# ADC_8CH.net
KiCad netlist of a schematic drawn in Altium Designer
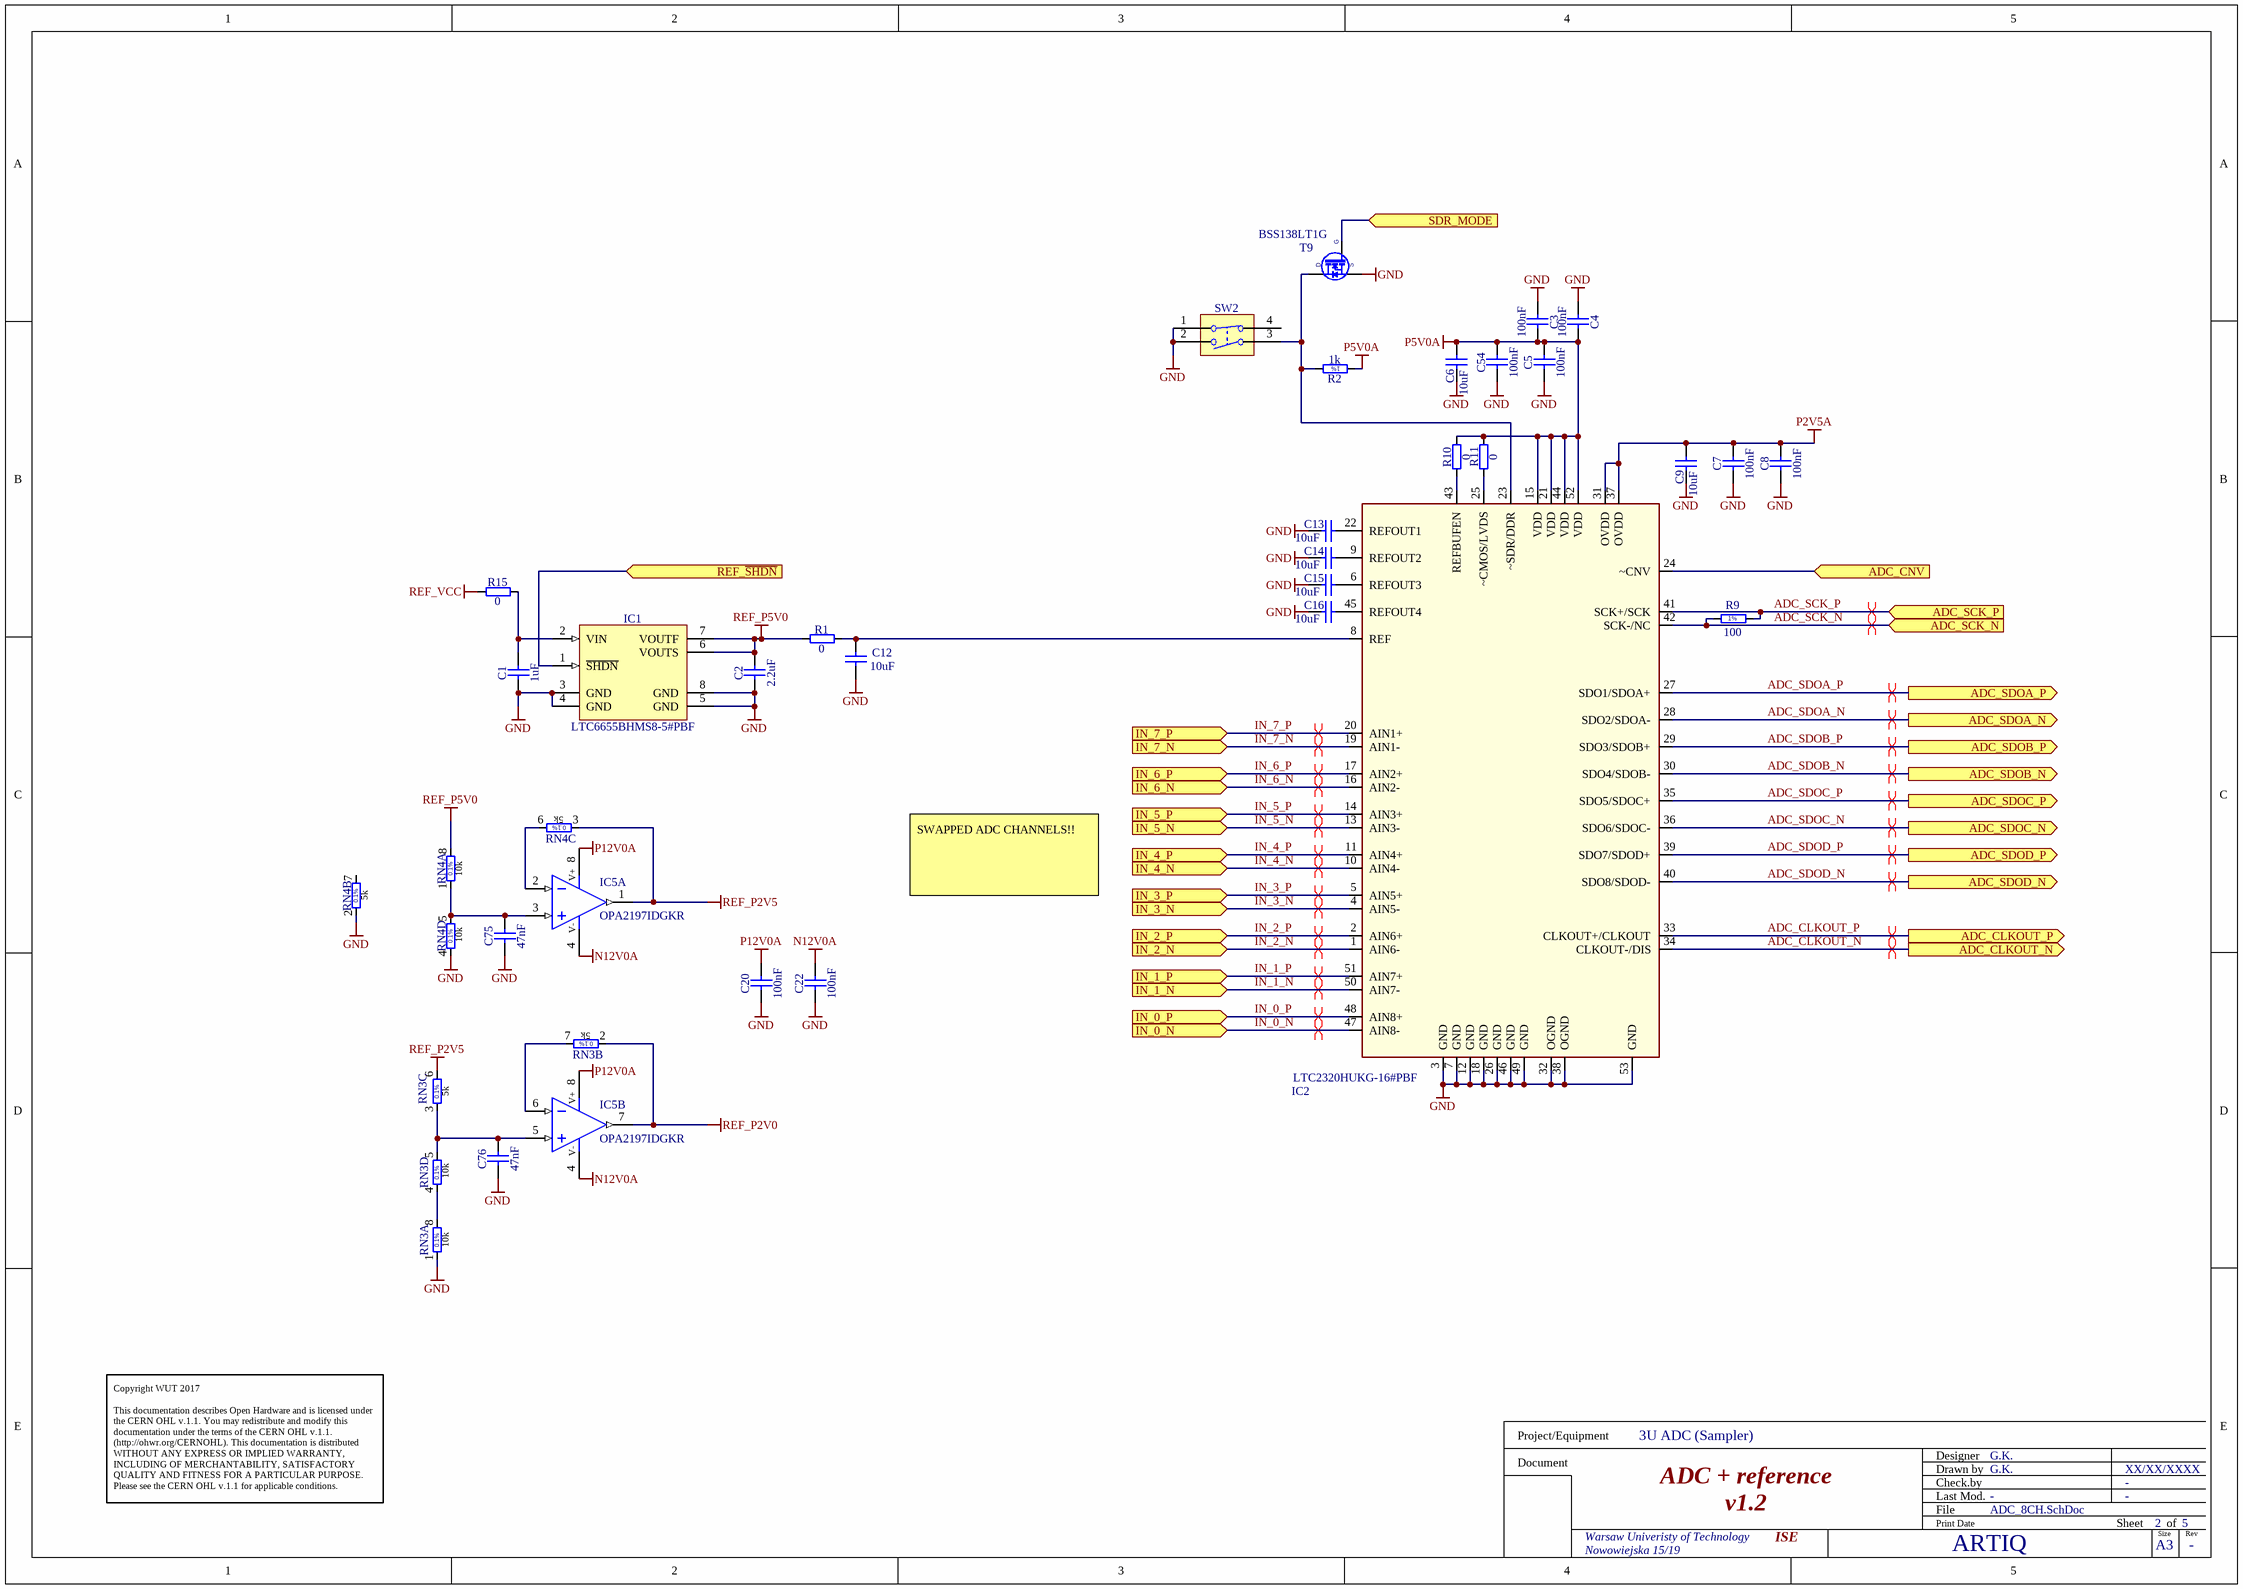
[diagram p0: ADC_8CH.SchDoc]

(export (version "E")
  (design (tool "Eeschema 10.0.6"))
  (components
    (comp (ref "C1")
      (value "1uF")
      (footprint "CAPC1608X87N")
      (description "Non-polarised capacitor")
      (fields
        (field (name "PART NUMBER") "CC0603_1UF_25V_10%_X7R")
        (field (name "VOLTAGE") "25V")
        (field (name "AUTHOR") "CERN DEM JLC")
      )
      (libsource (lib "Capacitors") (part "Capacitor - non polarized"))
    )
    (comp (ref "C2")
      (value "2.2uF")
      (footprint "CAPC1608X87N")
      (description "Non-polarised capacitor")
      (fields
        (field (name "PART NUMBER") "CC0603_2.2UF_16V_10%_X5R")
        (field (name "VOLTAGE") "16V")
        (field (name "AUTHOR") "CERN DEM JLC")
      )
      (libsource (lib "Capacitors") (part "Capacitor - non polarized"))
    )
    (comp (ref "C3")
      (value "100nF")
      (footprint "CAPC1608X87N")
      (description "Non-polarised capacitor")
      (fields
        (field (name "PART NUMBER") "CC0603_100NF_50V_10%_X7R")
        (field (name "VOLTAGE") "50V")
        (field (name "AUTHOR") "CERN DEM JLC")
      )
      (libsource (lib "Capacitors") (part "Capacitor - non polarized"))
    )
    (comp (ref "C4")
      (value "100nF")
      (footprint "CAPC1608X87N")
      (description "Non-polarised capacitor")
      (fields
        (field (name "PART NUMBER") "CC0603_100NF_50V_10%_X7R")
        (field (name "VOLTAGE") "50V")
        (field (name "AUTHOR") "CERN DEM JLC")
      )
      (libsource (lib "Capacitors") (part "Capacitor - non polarized"))
    )
    (comp (ref "C5")
      (value "100nF")
      (footprint "CAPC1608X87N")
      (description "Non-polarised capacitor")
      (fields
        (field (name "PART NUMBER") "CC0603_100NF_50V_10%_X7R")
        (field (name "VOLTAGE") "50V")
        (field (name "AUTHOR") "CERN DEM JLC")
      )
      (libsource (lib "Capacitors") (part "Capacitor - non polarized"))
    )
    (comp (ref "C6")
      (value "10uF")
      (footprint "CAPC2012X95N")
      (description "Non-polarised capacitor")
      (fields
        (field (name "PART NUMBER") "CC0805_10UF_25V_10%_X5R")
        (field (name "VOLTAGE") "25V")
        (field (name "AUTHOR") "CERN DEM JLC")
      )
      (libsource (lib "Capacitors") (part "Capacitor - non polarized"))
    )
    (comp (ref "C7")
      (value "100nF")
      (footprint "CAPC1608X87N")
      (description "Non-polarised capacitor")
      (fields
        (field (name "PART NUMBER") "CC0603_100NF_50V_10%_X7R")
        (field (name "VOLTAGE") "50V")
        (field (name "AUTHOR") "CERN DEM JLC")
      )
      (libsource (lib "Capacitors") (part "Capacitor - non polarized"))
    )
    (comp (ref "C8")
      (value "100nF")
      (footprint "CAPC1608X87N")
      (description "Non-polarised capacitor")
      (fields
        (field (name "PART NUMBER") "CC0603_100NF_50V_10%_X7R")
        (field (name "VOLTAGE") "50V")
        (field (name "AUTHOR") "CERN DEM JLC")
      )
      (libsource (lib "Capacitors") (part "Capacitor - non polarized"))
    )
    (comp (ref "C9")
      (value "10uF")
      (footprint "CAPC2012X95N")
      (description "Non-polarised capacitor")
      (fields
        (field (name "PART NUMBER") "CC0805_10UF_25V_10%_X5R")
        (field (name "VOLTAGE") "25V")
        (field (name "AUTHOR") "CERN DEM JLC")
      )
      (libsource (lib "Capacitors") (part "Capacitor - non polarized"))
    )
    (comp (ref "C12")
      (value "10uF")
      (footprint "CAPC2012X95N")
      (description "Non-polarised capacitor")
      (fields
        (field (name "PART NUMBER") "CC0805_10UF_25V_10%_X5R")
        (field (name "VOLTAGE") "25V")
        (field (name "AUTHOR") "CERN DEM JLC")
      )
      (libsource (lib "Capacitors") (part "Capacitor - non polarized"))
    )
    (comp (ref "C13")
      (value "10uF")
      (footprint "CAPC2012X95N")
      (description "Non-polarised capacitor")
      (fields
        (field (name "PART NUMBER") "CC0805_10UF_25V_10%_X5R")
        (field (name "VOLTAGE") "25V")
        (field (name "AUTHOR") "CERN DEM JLC")
      )
      (libsource (lib "Capacitors") (part "Capacitor - non polarized"))
    )
    (comp (ref "C14")
      (value "10uF")
      (footprint "CAPC2012X95N")
      (description "Non-polarised capacitor")
      (fields
        (field (name "PART NUMBER") "CC0805_10UF_25V_10%_X5R")
        (field (name "VOLTAGE") "25V")
        (field (name "AUTHOR") "CERN DEM JLC")
      )
      (libsource (lib "Capacitors") (part "Capacitor - non polarized"))
    )
    (comp (ref "C15")
      (value "10uF")
      (footprint "CAPC2012X95N")
      (description "Non-polarised capacitor")
      (fields
        (field (name "PART NUMBER") "CC0805_10UF_25V_10%_X5R")
        (field (name "VOLTAGE") "25V")
        (field (name "AUTHOR") "CERN DEM JLC")
      )
      (libsource (lib "Capacitors") (part "Capacitor - non polarized"))
    )
    (comp (ref "C16")
      (value "10uF")
      (footprint "CAPC2012X95N")
      (description "Non-polarised capacitor")
      (fields
        (field (name "PART NUMBER") "CC0805_10UF_25V_10%_X5R")
        (field (name "VOLTAGE") "25V")
        (field (name "AUTHOR") "CERN DEM JLC")
      )
      (libsource (lib "Capacitors") (part "Capacitor - non polarized"))
    )
    (comp (ref "C20")
      (value "100nF")
      (footprint "CAPC1005X55N")
      (description "Non-polarised capacitor")
      (fields
        (field (name "PART NUMBER") "CC0402_100NF_16V_10%_X5R")
        (field (name "VOLTAGE") "16V")
        (field (name "AUTHOR") "CERN DEM JLC")
      )
      (libsource (lib "Capacitors") (part "Capacitor - non polarized"))
    )
    (comp (ref "C22")
      (value "100nF")
      (footprint "CAPC1005X55N")
      (description "Non-polarised capacitor")
      (fields
        (field (name "PART NUMBER") "CC0402_100NF_16V_10%_X5R")
        (field (name "VOLTAGE") "16V")
        (field (name "AUTHOR") "CERN DEM JLC")
      )
      (libsource (lib "Capacitors") (part "Capacitor - non polarized"))
    )
    (comp (ref "C54")
      (value "100nF")
      (footprint "CAPC1608X87N")
      (description "Non-polarised capacitor")
      (fields
        (field (name "PART NUMBER") "CC0603_100NF_50V_10%_X7R")
        (field (name "VOLTAGE") "50V")
        (field (name "AUTHOR") "CERN DEM JLC")
      )
      (libsource (lib "Capacitors") (part "Capacitor - non polarized"))
    )
    (comp (ref "C75")
      (value "47nF")
      (footprint "CAPC2012X135N")
      (description "Non-polarised capacitor")
      (fields
        (field (name "PART NUMBER") "CC0805_47NF_25V_5%_C0G")
        (field (name "VOLTAGE") "25V")
        (field (name "AUTHOR") "CERN DEM JLC")
      )
      (libsource (lib "Capacitors") (part "Capacitor - non polarized"))
    )
    (comp (ref "C76")
      (value "47nF")
      (footprint "CAPC2012X135N")
      (description "Non-polarised capacitor")
      (fields
        (field (name "PART NUMBER") "CC0805_47NF_25V_5%_C0G")
        (field (name "VOLTAGE") "25V")
        (field (name "AUTHOR") "CERN DEM JLC")
      )
      (libsource (lib "Capacitors") (part "Capacitor - non polarized"))
    )
    (comp (ref "IC1")
      (value "LTC6655BHMS8-5#PBF")
      (footprint "SOP65P490X110-8N")
      (description "0.25ppm Noise, Low Drift Precision Buffered Voltage Reference")
      (fields (field (name "MANUFACTURER") "LINEAR TECHNOLOGY") (field (name "AUTHOR") "CERN DEM JLC"))
      (libsource (lib "ICs And Semiconductors") (part "LTC6655"))
    )
    (comp (ref "IC2")
      (value "LTC2320HUKG-16#PBF")
      (footprint "QFN50P700X800X80_HS-53M")
      (description "Octal, 16-Bit, 1.5Msps/Ch  Simultaneous Sampling ADC")
      (fields (field (name "MANUFACTURER") "LINEAR TECHNOLOGY") (field (name "AUTHOR") "GK"))
      (libsource (lib "LIBRARY_SCH") (part "ADC_LTC2320HUKG-16"))
    )
    (comp (ref "IC5")
      (value "OPA2197IDGKR")
      (footprint "SOP65P490X110-8N")
      (description "36-V, Precision, Rail-to-Rail Input Output, Low Offset Voltage Op Amp 8-VSSOP")
      (fields (field (name "MANUFACTURER") "TEXAS INSTRUMENTS") (field (name "AUTHOR") "GK"))
      (libsource (lib "LIBRARY_SCH") (part "OA_OPA2197IDGKR"))
    )
    (comp (ref "R1")
      (value "0")
      (footprint "RESC1005X40N")
      (description "Resistor")
      (fields
        (field (name "PART NUMBER") "R0402_0R_JUMPER")
        (field (name "MANUFACTURER") "GENERIC")
        (field (name "AUTHOR") "CERN DEM JLC")
      )
      (libsource (lib "Resistors") (part "Resistor"))
    )
    (comp (ref "R2")
      (value "1k")
      (footprint "RESC1608X55N")
      (description "Resistor - 1%")
      (fields
        (field (name "PART NUMBER") "R0603_1K_1%_0.1W_100PPM")
        (field (name "POWER") "0.1W")
        (field (name "AUTHOR") "CERN DEM JLC")
      )
      (libsource (lib "Resistors") (part "Resistor - 1%"))
    )
    (comp (ref "R9")
      (value "100")
      (footprint "RESC1005X40N")
      (description "Resistor - 1%")
      (fields
        (field (name "PART NUMBER") "R0402_100R_1%_0.1W_100PPM")
        (field (name "POWER") "0.1W")
        (field (name "AUTHOR") "CERN DEM JLC")
      )
      (libsource (lib "Resistors") (part "Resistor - 1%"))
    )
    (comp (ref "R10")
      (value "0")
      (footprint "RESC1005X40N")
      (description "Resistor")
      (fields
        (field (name "PART NUMBER") "R0402_0R_JUMPER")
        (field (name "MANUFACTURER") "GENERIC")
        (field (name "AUTHOR") "CERN DEM JLC")
      )
      (libsource (lib "Resistors") (part "Resistor"))
    )
    (comp (ref "R11")
      (value "0")
      (footprint "RESC1005X40N")
      (description "Resistor")
      (fields
        (field (name "PART NUMBER") "R0402_0R_JUMPER")
        (field (name "MANUFACTURER") "GENERIC")
        (field (name "AUTHOR") "CERN DEM JLC")
      )
      (libsource (lib "Resistors") (part "Resistor"))
    )
    (comp (ref "R15")
      (value "0")
      (footprint "RESC1005X40N")
      (description "Resistor")
      (fields
        (field (name "PART NUMBER") "R0402_0R_JUMPER")
        (field (name "MANUFACTURER") "GENERIC")
        (field (name "AUTHOR") "CERN DEM JLC")
      )
      (libsource (lib "Resistors") (part "Resistor"))
    )
    (comp (ref "RN3")
      (value "10k 5K 5K 10K")
      (footprint "SOIC127P600X175-8N")
      (description "DIL8 Resistor Network 4 Resistors 10k-5k-5k-10k 0.1%")
      (fields
        (field (name "PART NUMBER") "RN_10K_5K_VISHAY_AORN2-1AT3")
        (field (name "POWER") "4x0.1W")
        (field (name "AUTHOR") "CERN DEM JLC")
      )
      (libsource (lib "Resistors") (part "RN DIL8_4xR_10k-5k-5k-10k_0.1%"))
    )
    (comp (ref "RN4")
      (value "10k 5K 5K 10K")
      (footprint "SOIC127P600X175-8N")
      (description "DIL8 Resistor Network 4 Resistors 10k-5k-5k-10k 0.1%")
      (fields
        (field (name "PART NUMBER") "RN_10K_5K_VISHAY_AORN2-1AT3")
        (field (name "POWER") "4x0.1W")
        (field (name "AUTHOR") "CERN DEM JLC")
      )
      (libsource (lib "Resistors") (part "RN DIL8_4xR_10k-5k-5k-10k_0.1%"))
    )
    (comp (ref "SW2")
      (value "Switch")
      (footprint "SW_CTS_204-121ST")
      (description "2x SPST DIP Switch 1NO + 1NF")
      (fields
        (field (name "PART NUMBER") "SW_CTS_204-121ST")
        (field (name "MANUFACTURER") "CTS")
        (field (name "AUTHOR") "CERN DEM JLC")
      )
      (libsource (lib "Eletro-mechanical") (part "SW_CTS_204-121ST"))
    )
    (comp (ref "T9")
      (value "BSS138LT1G")
      (footprint "SOT95P240X110-3N")
      (description "N-CHANNEL MOSFET WITH DIODE")
      (fields (field (name "MANUFACTURER") "ON SEMICONDUCTOR") (field (name "AUTHOR") "CERN DEM JLC"))
      (libsource (lib "ICs And Semiconductors") (part "N-MOSFET-D 1G 2S 3D"))
    )
  )
  (nets
    (net (code "1") (name "/ADC_CLKOUT_N") (class "Default")
      (node (ref "IC2") (pin "34") (pinfunction "CLKOUT-/DIS_34") (pintype "passive"))
    )
    (net (code "2") (name "/ADC_CLKOUT_P") (class "Default")
      (node (ref "IC2") (pin "33") (pinfunction "CLKOUT+/CLKOUT_33") (pintype "passive"))
    )
    (net (code "3") (name "/ADC_CNV") (class "Default")
      (node (ref "IC2") (pin "24") (pinfunction "~CNV_24") (pintype "passive"))
    )
    (net (code "4") (name "/ADC_SCK_N") (class "Default")
      (node (ref "IC2") (pin "42") (pinfunction "SCK-/NC_42") (pintype "passive"))
      (node (ref "R9") (pin "1") (pinfunction "1_1") (pintype "passive"))
    )
    (net (code "5") (name "/ADC_SCK_P") (class "Default")
      (node (ref "IC2") (pin "41") (pinfunction "SCK+/SCK_41") (pintype "passive"))
      (node (ref "R9") (pin "2") (pinfunction "2_2") (pintype "passive"))
    )
    (net (code "6") (name "/ADC_SDOA_N") (class "Default")
      (node (ref "IC2") (pin "28") (pinfunction "SDO2/SDOA-_28") (pintype "passive"))
    )
    (net (code "7") (name "/ADC_SDOA_P") (class "Default")
      (node (ref "IC2") (pin "27") (pinfunction "SDO1/SDOA+_27") (pintype "passive"))
    )
    (net (code "8") (name "/ADC_SDOB_N") (class "Default")
      (node (ref "IC2") (pin "30") (pinfunction "SDO4/SDOB-_30") (pintype "passive"))
    )
    (net (code "9") (name "/ADC_SDOB_P") (class "Default")
      (node (ref "IC2") (pin "29") (pinfunction "SDO3/SDOB+_29") (pintype "passive"))
    )
    (net (code "10") (name "/ADC_SDOC_N") (class "Default")
      (node (ref "IC2") (pin "36") (pinfunction "SDO6/SDOC-_36") (pintype "passive"))
    )
    (net (code "11") (name "/ADC_SDOC_P") (class "Default")
      (node (ref "IC2") (pin "35") (pinfunction "SDO5/SDOC+_35") (pintype "passive"))
    )
    (net (code "12") (name "/ADC_SDOD_N") (class "Default")
      (node (ref "IC2") (pin "40") (pinfunction "SDO8/SDOD-_40") (pintype "passive"))
    )
    (net (code "13") (name "/ADC_SDOD_P") (class "Default")
      (node (ref "IC2") (pin "39") (pinfunction "SDO7/SDOD+_39") (pintype "passive"))
    )
    (net (code "14") (name "/IN_0_N") (class "Default")
      (node (ref "IC2") (pin "47") (pinfunction "AIN8-_47") (pintype "passive"))
    )
    (net (code "15") (name "/IN_0_P") (class "Default")
      (node (ref "IC2") (pin "48") (pinfunction "AIN8+_48") (pintype "passive"))
    )
    (net (code "16") (name "/IN_1_N") (class "Default")
      (node (ref "IC2") (pin "50") (pinfunction "AIN7-_50") (pintype "passive"))
    )
    (net (code "17") (name "/IN_1_P") (class "Default")
      (node (ref "IC2") (pin "51") (pinfunction "AIN7+_51") (pintype "passive"))
    )
    (net (code "18") (name "/IN_2_N") (class "Default")
      (node (ref "IC2") (pin "1") (pinfunction "AIN6-_1") (pintype "passive"))
    )
    (net (code "19") (name "/IN_2_P") (class "Default")
      (node (ref "IC2") (pin "2") (pinfunction "AIN6+_2") (pintype "passive"))
    )
    (net (code "20") (name "/IN_3_N") (class "Default")
      (node (ref "IC2") (pin "4") (pinfunction "AIN5-_4") (pintype "passive"))
    )
    (net (code "21") (name "/IN_3_P") (class "Default")
      (node (ref "IC2") (pin "5") (pinfunction "AIN5+_5") (pintype "passive"))
    )
    (net (code "22") (name "/IN_4_N") (class "Default")
      (node (ref "IC2") (pin "10") (pinfunction "AIN4-_10") (pintype "passive"))
    )
    (net (code "23") (name "/IN_4_P") (class "Default")
      (node (ref "IC2") (pin "11") (pinfunction "AIN4+_11") (pintype "passive"))
    )
    (net (code "24") (name "/IN_5_N") (class "Default")
      (node (ref "IC2") (pin "13") (pinfunction "AIN3-_13") (pintype "passive"))
    )
    (net (code "25") (name "/IN_5_P") (class "Default")
      (node (ref "IC2") (pin "14") (pinfunction "AIN3+_14") (pintype "passive"))
    )
    (net (code "26") (name "/IN_6_N") (class "Default")
      (node (ref "IC2") (pin "16") (pinfunction "AIN2-_16") (pintype "passive"))
    )
    (net (code "27") (name "/IN_6_P") (class "Default")
      (node (ref "IC2") (pin "17") (pinfunction "AIN2+_17") (pintype "passive"))
    )
    (net (code "28") (name "/IN_7_N") (class "Default")
      (node (ref "IC2") (pin "19") (pinfunction "AIN1-_19") (pintype "passive"))
    )
    (net (code "29") (name "/IN_7_P") (class "Default")
      (node (ref "IC2") (pin "20") (pinfunction "AIN1+_20") (pintype "passive"))
    )
    (net (code "30") (name "/REF_~{SHDN}") (class "Default")
      (node (ref "IC1") (pin "1") (pinfunction "~{SHDN}_1") (pintype "input"))
    )
    (net (code "31") (name "/SDR_MODE") (class "Default")
      (node (ref "T9") (pin "1") (pinfunction "G_1") (pintype "passive"))
    )
    (net (code "32") (name "GND") (class "Default")
      (node (ref "C1") (pin "1") (pinfunction "1_1") (pintype "passive"))
      (node (ref "C12") (pin "1") (pinfunction "1_1") (pintype "passive"))
      (node (ref "C13") (pin "1") (pinfunction "1_1") (pintype "passive"))
      (node (ref "C14") (pin "1") (pinfunction "1_1") (pintype "passive"))
      (node (ref "C15") (pin "1") (pinfunction "1_1") (pintype "passive"))
      (node (ref "C16") (pin "1") (pinfunction "1_1") (pintype "passive"))
      (node (ref "C2") (pin "1") (pinfunction "1_1") (pintype "passive"))
      (node (ref "C20") (pin "1") (pinfunction "1_1") (pintype "passive"))
      (node (ref "C22") (pin "1") (pinfunction "1_1") (pintype "passive"))
      (node (ref "C3") (pin "1") (pinfunction "1_1") (pintype "passive"))
      (node (ref "C4") (pin "1") (pinfunction "1_1") (pintype "passive"))
      (node (ref "C5") (pin "1") (pinfunction "1_1") (pintype "passive"))
      (node (ref "C54") (pin "1") (pinfunction "1_1") (pintype "passive"))
      (node (ref "C6") (pin "1") (pinfunction "1_1") (pintype "passive"))
      (node (ref "C7") (pin "1") (pinfunction "1_1") (pintype "passive"))
      (node (ref "C75") (pin "1") (pinfunction "1_1") (pintype "passive"))
      (node (ref "C76") (pin "1") (pinfunction "1_1") (pintype "passive"))
      (node (ref "C8") (pin "1") (pinfunction "1_1") (pintype "passive"))
      (node (ref "C9") (pin "1") (pinfunction "1_1") (pintype "passive"))
      (node (ref "IC1") (pin "3") (pinfunction "GND_3") (pintype "power_in"))
      (node (ref "IC1") (pin "4") (pinfunction "GND_4") (pintype "power_in"))
      (node (ref "IC1") (pin "5") (pinfunction "GND_5") (pintype "power_in"))
      (node (ref "IC1") (pin "8") (pinfunction "GND_8") (pintype "power_in"))
      (node (ref "IC2") (pin "12") (pinfunction "GND_12") (pintype "passive"))
      (node (ref "IC2") (pin "18") (pinfunction "GND_18") (pintype "passive"))
      (node (ref "IC2") (pin "26") (pinfunction "GND_26") (pintype "passive"))
      (node (ref "IC2") (pin "3") (pinfunction "GND_3") (pintype "passive"))
      (node (ref "IC2") (pin "32") (pinfunction "OGND_32") (pintype "passive"))
      (node (ref "IC2") (pin "38") (pinfunction "OGND_38") (pintype "passive"))
      (node (ref "IC2") (pin "46") (pinfunction "GND_46") (pintype "passive"))
      (node (ref "IC2") (pin "49") (pinfunction "GND_49") (pintype "passive"))
      (node (ref "IC2") (pin "53") (pinfunction "GND_53") (pintype "passive"))
      (node (ref "IC2") (pin "7") (pinfunction "GND_7") (pintype "passive"))
      (node (ref "RN3") (pin "1") (pinfunction "1_1") (pintype "passive"))
      (node (ref "RN4") (pin "2") (pinfunction "2_2") (pintype "passive"))
      (node (ref "RN4") (pin "4") (pinfunction "4_4") (pintype "passive"))
      (node (ref "SW2") (pin "1") (pinfunction "1_1") (pintype "passive"))
      (node (ref "SW2") (pin "2") (pinfunction "2_2") (pintype "passive"))
      (node (ref "T9") (pin "2") (pinfunction "S_2") (pintype "passive"))
    )
    (net (code "33") (name "N12V0A") (class "Default")
      (node (ref "C22") (pin "2") (pinfunction "2_2") (pintype "passive"))
      (node (ref "IC5") (pin "4") (pinfunction "V-_4") (pintype "power_in"))
    )
    (net (code "34") (name "Net-(IC1-VIN)") (class "Default")
      (node (ref "C1") (pin "2") (pinfunction "2_2") (pintype "passive"))
      (node (ref "IC1") (pin "2") (pinfunction "VIN_2") (pintype "input"))
      (node (ref "R15") (pin "2") (pinfunction "2_2") (pintype "passive"))
    )
    (net (code "35") (name "Net-(IC2-REF)") (class "Default")
      (node (ref "C12") (pin "2") (pinfunction "2_2") (pintype "passive"))
      (node (ref "IC2") (pin "8") (pinfunction "REF_8") (pintype "passive"))
      (node (ref "R1") (pin "2") (pinfunction "2_2") (pintype "passive"))
    )
    (net (code "36") (name "Net-(IC2-REFBUFEN)") (class "Default")
      (node (ref "IC2") (pin "43") (pinfunction "REFBUFEN_43") (pintype "passive"))
      (node (ref "R10") (pin "1") (pinfunction "1_1") (pintype "passive"))
    )
    (net (code "37") (name "Net-(IC2-REFOUT1)") (class "Default")
      (node (ref "C13") (pin "2") (pinfunction "2_2") (pintype "passive"))
      (node (ref "IC2") (pin "22") (pinfunction "REFOUT1_22") (pintype "passive"))
    )
    (net (code "38") (name "Net-(IC2-REFOUT2)") (class "Default")
      (node (ref "C14") (pin "2") (pinfunction "2_2") (pintype "passive"))
      (node (ref "IC2") (pin "9") (pinfunction "REFOUT2_9") (pintype "passive"))
    )
    (net (code "39") (name "Net-(IC2-REFOUT3)") (class "Default")
      (node (ref "C15") (pin "2") (pinfunction "2_2") (pintype "passive"))
      (node (ref "IC2") (pin "6") (pinfunction "REFOUT3_6") (pintype "passive"))
    )
    (net (code "40") (name "Net-(IC2-REFOUT4)") (class "Default")
      (node (ref "C16") (pin "2") (pinfunction "2_2") (pintype "passive"))
      (node (ref "IC2") (pin "45") (pinfunction "REFOUT4_45") (pintype "passive"))
    )
    (net (code "41") (name "Net-(IC2-~CMOS{slash}LVDS)") (class "Default")
      (node (ref "IC2") (pin "25") (pinfunction "~CMOS/LVDS_25") (pintype "passive"))
      (node (ref "R11") (pin "1") (pinfunction "1_1") (pintype "passive"))
    )
    (net (code "42") (name "Net-(IC2-~SDR{slash}DDR)") (class "Default")
      (node (ref "IC2") (pin "23") (pinfunction "~SDR/DDR_23") (pintype "passive"))
      (node (ref "R2") (pin "2") (pinfunction "2_2") (pintype "passive"))
      (node (ref "SW2") (pin "3") (pinfunction "3_3") (pintype "passive"))
      (node (ref "T9") (pin "3") (pinfunction "D_3") (pintype "passive"))
    )
    (net (code "43") (name "Net-(IC5A-IN+)") (class "Default")
      (node (ref "C75") (pin "2") (pinfunction "2_2") (pintype "passive"))
      (node (ref "IC5") (pin "3") (pinfunction "IN+_3") (pintype "input"))
      (node (ref "RN4") (pin "1") (pinfunction "1_1") (pintype "passive"))
      (node (ref "RN4") (pin "5") (pinfunction "5_5") (pintype "passive"))
    )
    (net (code "44") (name "Net-(IC5A-IN-)") (class "Default")
      (node (ref "IC5") (pin "2") (pinfunction "IN-_2") (pintype "input"))
      (node (ref "RN4") (pin "6") (pinfunction "6_6") (pintype "passive"))
    )
    (net (code "45") (name "Net-(IC5B-IN+)") (class "Default")
      (node (ref "C76") (pin "2") (pinfunction "2_2") (pintype "passive"))
      (node (ref "IC5") (pin "5") (pinfunction "IN+_5") (pintype "input"))
      (node (ref "RN3") (pin "3") (pinfunction "3_3") (pintype "passive"))
      (node (ref "RN3") (pin "5") (pinfunction "5_5") (pintype "passive"))
    )
    (net (code "46") (name "Net-(IC5B-IN-)") (class "Default")
      (node (ref "IC5") (pin "6") (pinfunction "IN-_6") (pintype "input"))
      (node (ref "RN3") (pin "7") (pinfunction "7_7") (pintype "passive"))
    )
    (net (code "47") (name "Net-(RN3-Pad4)") (class "Default")
      (node (ref "RN3") (pin "4") (pinfunction "4_4") (pintype "passive"))
      (node (ref "RN3") (pin "8") (pinfunction "8_8") (pintype "passive"))
    )
    (net (code "48") (name "P2V5A") (class "Default")
      (node (ref "C7") (pin "2") (pinfunction "2_2") (pintype "passive"))
      (node (ref "C8") (pin "2") (pinfunction "2_2") (pintype "passive"))
      (node (ref "C9") (pin "2") (pinfunction "2_2") (pintype "passive"))
      (node (ref "IC2") (pin "31") (pinfunction "OVDD_31") (pintype "passive"))
      (node (ref "IC2") (pin "37") (pinfunction "OVDD_37") (pintype "passive"))
    )
    (net (code "49") (name "P5V0A") (class "Default")
      (node (ref "C3") (pin "2") (pinfunction "2_2") (pintype "passive"))
      (node (ref "C4") (pin "2") (pinfunction "2_2") (pintype "passive"))
      (node (ref "C5") (pin "2") (pinfunction "2_2") (pintype "passive"))
      (node (ref "C54") (pin "2") (pinfunction "2_2") (pintype "passive"))
      (node (ref "C6") (pin "2") (pinfunction "2_2") (pintype "passive"))
      (node (ref "IC2") (pin "15") (pinfunction "VDD_15") (pintype "passive"))
      (node (ref "IC2") (pin "21") (pinfunction "VDD_21") (pintype "passive"))
      (node (ref "IC2") (pin "44") (pinfunction "VDD_44") (pintype "passive"))
      (node (ref "IC2") (pin "52") (pinfunction "VDD_52") (pintype "passive"))
      (node (ref "R10") (pin "2") (pinfunction "2_2") (pintype "passive"))
      (node (ref "R11") (pin "2") (pinfunction "2_2") (pintype "passive"))
      (node (ref "R2") (pin "1") (pinfunction "1_1") (pintype "passive"))
    )
    (net (code "50") (name "P12V0A") (class "Default")
      (node (ref "C20") (pin "2") (pinfunction "2_2") (pintype "passive"))
      (node (ref "IC5") (pin "8") (pinfunction "V+_8") (pintype "power_in"))
    )
    (net (code "51") (name "REF_P2V0") (class "Default")
      (node (ref "IC5") (pin "7") (pinfunction "OUT_7") (pintype "output"))
      (node (ref "RN3") (pin "2") (pinfunction "2_2") (pintype "passive"))
    )
    (net (code "52") (name "REF_P2V5") (class "Default")
      (node (ref "IC5") (pin "1") (pinfunction "OUT_1") (pintype "output"))
      (node (ref "RN3") (pin "6") (pinfunction "6_6") (pintype "passive"))
      (node (ref "RN4") (pin "3") (pinfunction "3_3") (pintype "passive"))
    )
    (net (code "53") (name "REF_P5V0") (class "Default")
      (node (ref "C2") (pin "2") (pinfunction "2_2") (pintype "passive"))
      (node (ref "IC1") (pin "6") (pinfunction "VOUTS_6") (pintype "power_in"))
      (node (ref "IC1") (pin "7") (pinfunction "VOUTF_7") (pintype "power_in"))
      (node (ref "R1") (pin "1") (pinfunction "1_1") (pintype "passive"))
      (node (ref "RN4") (pin "8") (pinfunction "8_8") (pintype "passive"))
    )
    (net (code "54") (name "REF_VCC") (class "Default")
      (node (ref "R15") (pin "1") (pinfunction "1_1") (pintype "passive"))
    )
    (net (code "55") (name "unconnected-(RN4-Pad7)") (class "Default")
      (node (ref "RN4") (pin "7") (pinfunction "7_7") (pintype "passive"))
    )
    (net (code "56") (name "unconnected-(SW2-Pad4)") (class "Default")
      (node (ref "SW2") (pin "4") (pinfunction "4_4") (pintype "passive"))
    )
  )
)
